# hardware.net
KiCad netlist of a schematic drawn in Altium Designer
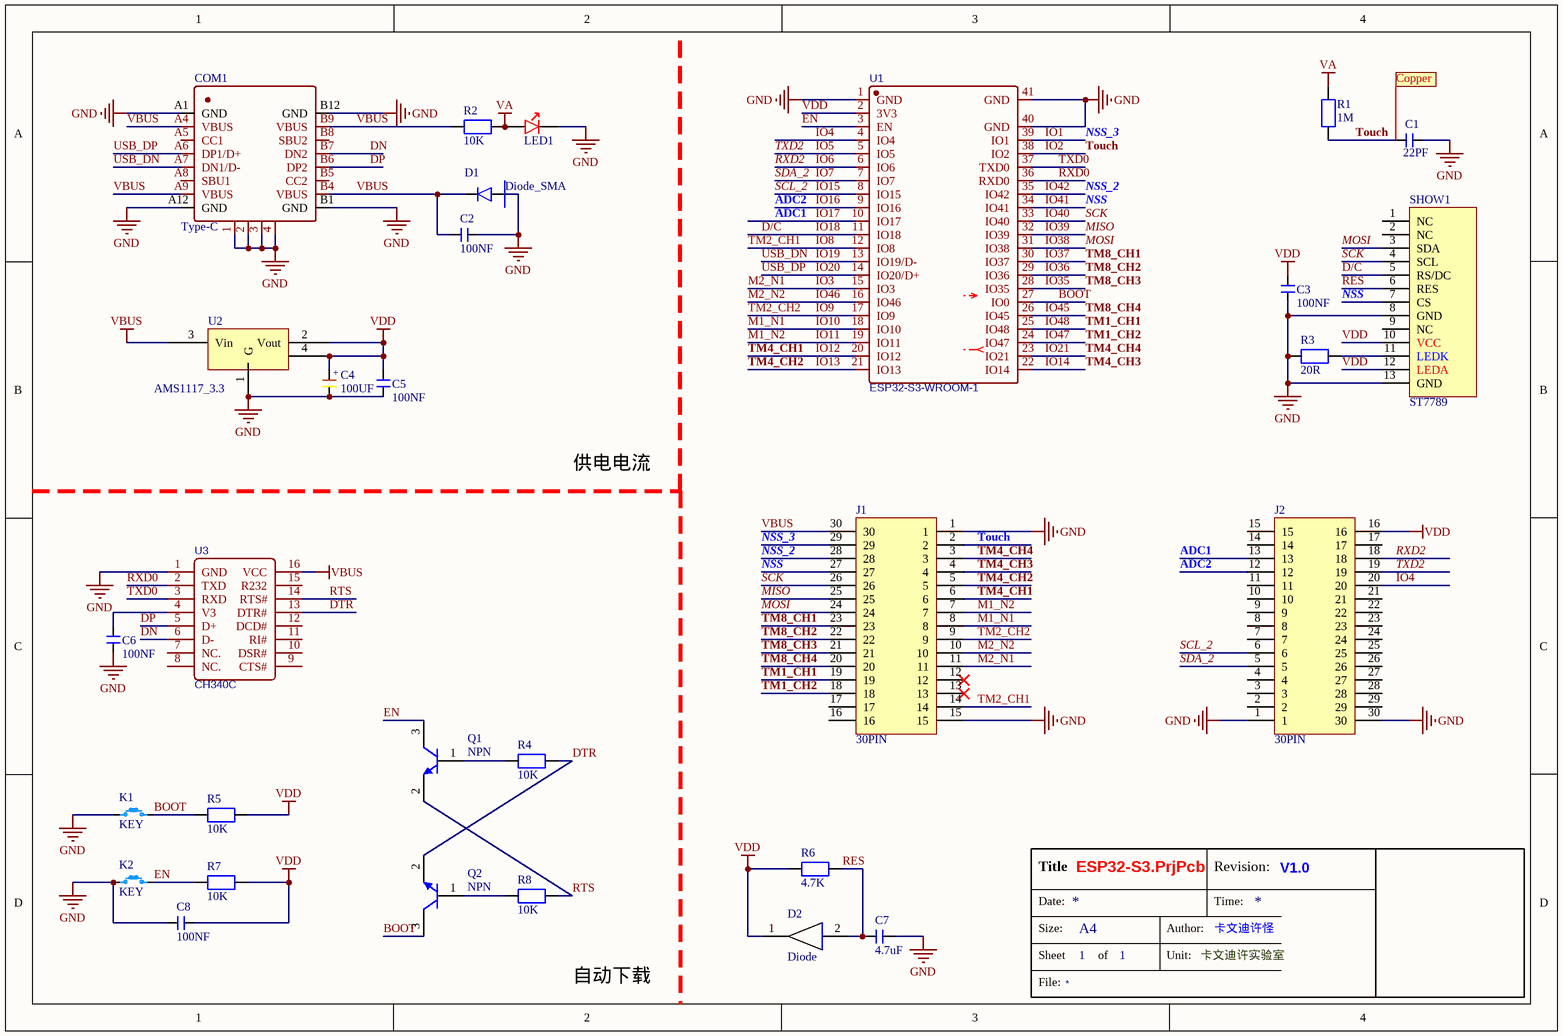
[diagram p0: hardware.SchDoc]

(export (version "E")
  (design (tool "Eeschema 10.0.6"))
  (components
    (comp (ref "C1")
      (value "22PF")
      (footprint "CAP_0603")
      (description "CAP  12~50V")
      (libsource (lib "User") (part "CAP"))
    )
    (comp (ref "C2")
      (value "100NF")
      (footprint "CAP_0603")
      (description "CAP  12~50V")
      (libsource (lib "User") (part "CAP"))
    )
    (comp (ref "C3")
      (value "100NF")
      (footprint "CAP_0603")
      (description "CAP  12~50V")
      (libsource (lib "User") (part "CAP"))
    )
    (comp (ref "C4")
      (value "100UF")
      (footprint "CAP_3528_B")
      (description "CAP  6~12V  钽电容")
      (libsource (lib "User") (part "CAP_TA"))
    )
    (comp (ref "C5")
      (value "100NF")
      (footprint "CAP_0603")
      (description "CAP  12~50V")
      (libsource (lib "User") (part "CAP"))
    )
    (comp (ref "C6")
      (value "100NF")
      (footprint "CAP_0603")
      (description "CAP  12~50V")
      (libsource (lib "User") (part "CAP"))
    )
    (comp (ref "C7")
      (value "4.7uF")
      (footprint "CAP_0603")
      (description "CAP")
      (libsource (lib "Schlib1") (part "CAP_SDM"))
    )
    (comp (ref "C8")
      (value "100NF")
      (footprint "CAP_0603")
      (description "CAP  12~50V")
      (libsource (lib "User") (part "CAP"))
    )
    (comp (ref "COM1")
      (value "Type-C")
      (footprint "USB-Type-C_16A")
      (description "USB")
      (libsource (lib "User") (part "USB-type_c"))
    )
    (comp (ref "D1")
      (value "Diode_SMA")
      (footprint "DIODE_SOD123")
      (description "Diode_肖特基")
      (libsource (lib "User") (part "Diode-SM"))
    )
    (comp (ref "D2")
      (value "Diode")
      (footprint "SOD123")
      (description "开关二极管")
      (libsource (lib "Schlib1") (part "Diode-SOD"))
    )
    (comp (ref "J1")
      (value "30PIN")
      (footprint "BTB_Double_30Pin_Up")
      (libsource (lib "") (part "BTB_DOUBLE_30PIN_1"))
    )
    (comp (ref "J2")
      (value "30PIN")
      (footprint "BTB_Double_30Pin_Up")
      (libsource (lib "User") (part "BTB_DOUBLE_30PIN"))
    )
    (comp (ref "K1")
      (value "KEY")
      (footprint "SW_PB_3X6")
      (description "Key")
      (libsource (lib "User") (part "KEY"))
    )
    (comp (ref "K2")
      (value "KEY")
      (footprint "SW_PB_3X6")
      (description "Key")
      (libsource (lib "User") (part "KEY"))
    )
    (comp (ref "LED1")
      (value "LED_R/G/B/Y")
      (footprint "LED_0603_R")
      (description "LED")
      (libsource (lib "User") (part "LED"))
    )
    (comp (ref "Q1") (value "NPN") (footprint "SOT23_3") (libsource (lib "User") (part "NPN")))
    (comp (ref "Q2") (value "NPN") (footprint "SOT23_3") (libsource (lib "User") (part "NPN")))
    (comp (ref "R1")
      (value "1M")
      (footprint "RESC_0603_2")
      (description "RES 贴片")
      (libsource (lib "User") (part "RES_S"))
    )
    (comp (ref "R2")
      (value "10K")
      (footprint "RESC_0603_2")
      (description "RES 贴片")
      (libsource (lib "User") (part "RES_S"))
    )
    (comp (ref "R3")
      (value "20R")
      (footprint "RESC_0603_2")
      (description "RES 贴片")
      (libsource (lib "User") (part "RES_S"))
    )
    (comp (ref "R4")
      (value "10K")
      (footprint "RESC_0603_2")
      (description "RES 贴片")
      (libsource (lib "User") (part "RES_S"))
    )
    (comp (ref "R5")
      (value "10K")
      (footprint "RESC_0603_2")
      (description "RES 贴片")
      (libsource (lib "User") (part "RES_S"))
    )
    (comp (ref "R6")
      (value "4.7K")
      (footprint "RESC_0603_2")
      (description "RES 贴片")
      (libsource (lib "User") (part "RES_S"))
    )
    (comp (ref "R7")
      (value "10K")
      (footprint "RESC_0603_2")
      (description "RES 贴片")
      (libsource (lib "User") (part "RES_S"))
    )
    (comp (ref "R8")
      (value "10K")
      (footprint "RESC_0603_2")
      (description "RES 贴片")
      (libsource (lib "User") (part "RES_S"))
    )
    (comp (ref "SHOW1")
      (value "ST7789")
      (footprint "LCD_1.14")
      (description "SHOW")
      (libsource (lib "User") (part "LCD_1.14"))
    )
    (comp (ref "U1")
      (value "ESP32-S3-WROOM-1")
      (footprint "ESP32-S3-WROOM-1")
      (fields
        (field (name "BOM_SUPPLIER PART") "C473005")
        (field (name "BOM_MANUFACTURER PART") "ESP32-SOLO-1")
        (field (name "CONTRIBUTOR") "LCSC")
      )
      (libsource (lib "User") (part "ESP32-S3-WROOM-1"))
    )
    (comp (ref "U2")
      (value "AMS1117_3.3")
      (footprint "SOT223_3")
      (description "DC-DC")
      (libsource (lib "User") (part "AMS1117_3.3"))
    )
    (comp (ref "U3")
      (value "CH340C")
      (footprint "SOIC_16")
      (fields (field (name "BOM_SUPPLIER PART") "C84681"))
      (libsource (lib "User") (part "CH340C"))
    )
  )
  (nets
    (net (code "1") (name "/ADC1") (class "Default")
      (node (ref "J2") (pin "13") (pinfunction "13_13") (pintype "passive"))
      (node (ref "U1") (pin "10") (pinfunction "IO17_10") (pintype "passive"))
    )
    (net (code "2") (name "/ADC2") (class "Default")
      (node (ref "J2") (pin "12") (pinfunction "12_12") (pintype "passive"))
      (node (ref "U1") (pin "9") (pinfunction "IO16_9") (pintype "passive"))
    )
    (net (code "3") (name "/BOOT") (class "Default")
      (node (ref "K1") (pin "1") (pintype "passive"))
      (node (ref "Q2") (pin "3") (pinfunction "C_3") (pintype "passive"))
      (node (ref "R5") (pin "1") (pinfunction "1_1") (pintype "passive"))
      (node (ref "U1") (pin "27") (pinfunction "IO0_27") (pintype "passive"))
    )
    (net (code "4") (name "/DN") (class "Default")
      (node (ref "COM1") (pin "B7") (pinfunction "DN2_B7") (pintype "passive"))
      (node (ref "U3") (pin "6") (pinfunction "D-_6") (pintype "passive"))
    )
    (net (code "5") (name "/DP") (class "Default")
      (node (ref "COM1") (pin "B6") (pinfunction "DP2_B6") (pintype "passive"))
      (node (ref "U3") (pin "5") (pinfunction "D+_5") (pintype "passive"))
    )
    (net (code "6") (name "/DTR") (class "Default")
      (node (ref "Q2") (pin "2") (pinfunction "E_2") (pintype "passive"))
      (node (ref "R4") (pin "2") (pinfunction "2_2") (pintype "passive"))
      (node (ref "U3") (pin "13") (pinfunction "DTR#_13") (pintype "passive"))
    )
    (net (code "7") (name "/D{slash}C") (class "Default")
      (node (ref "SHOW1") (pin "5") (pinfunction "RS/DC_5") (pintype "passive"))
      (node (ref "U1") (pin "11") (pinfunction "IO18_11") (pintype "passive"))
    )
    (net (code "8") (name "/EN") (class "Default")
      (node (ref "K2") (pin "1") (pintype "passive"))
      (node (ref "Q1") (pin "3") (pinfunction "C_3") (pintype "passive"))
      (node (ref "R7") (pin "1") (pinfunction "1_1") (pintype "passive"))
      (node (ref "U1") (pin "3") (pinfunction "EN_3") (pintype "passive"))
    )
    (net (code "9") (name "/IO1") (class "Default")
      (node (ref "J1") (pin "29") (pinfunction "29_29") (pintype "passive"))
      (node (ref "U1") (pin "39") (pinfunction "IO1_39") (pintype "passive"))
    )
    (net (code "10") (name "/IO2") (class "Default")
      (node (ref "C1") (pin "1") (pinfunction "0_1") (pintype "passive"))
      (node (ref "J1") (pin "2") (pinfunction "2_2") (pintype "passive"))
      (node (ref "R1") (pin "1") (pinfunction "1_1") (pintype "passive"))
      (node (ref "U1") (pin "38") (pinfunction "IO2_38") (pintype "passive"))
    )
    (net (code "11") (name "/IO3") (class "Default")
      (node (ref "J1") (pin "11") (pinfunction "11_11") (pintype "passive"))
      (node (ref "U1") (pin "15") (pinfunction "IO3_15") (pintype "passive"))
    )
    (net (code "12") (name "/IO4") (class "Default")
      (node (ref "J2") (pin "20") (pinfunction "20_20") (pintype "passive"))
      (node (ref "U1") (pin "4") (pinfunction "IO4_4") (pintype "passive"))
    )
    (net (code "13") (name "/IO5") (class "Default")
      (node (ref "J2") (pin "19") (pinfunction "19_19") (pintype "passive"))
      (node (ref "U1") (pin "5") (pinfunction "IO5_5") (pintype "passive"))
    )
    (net (code "14") (name "/IO6") (class "Default")
      (node (ref "J2") (pin "18") (pinfunction "18_18") (pintype "passive"))
      (node (ref "U1") (pin "6") (pinfunction "IO6_6") (pintype "passive"))
    )
    (net (code "15") (name "/IO7") (class "Default")
      (node (ref "J2") (pin "5") (pinfunction "5_5") (pintype "passive"))
      (node (ref "U1") (pin "7") (pinfunction "IO7_7") (pintype "passive"))
    )
    (net (code "16") (name "/IO8") (class "Default")
      (node (ref "J1") (pin "14") (pinfunction "14_14") (pintype "passive"))
      (node (ref "U1") (pin "12") (pinfunction "IO8_12") (pintype "passive"))
    )
    (net (code "17") (name "/IO9") (class "Default")
      (node (ref "J1") (pin "9") (pinfunction "9_9") (pintype "passive"))
      (node (ref "U1") (pin "17") (pinfunction "IO9_17") (pintype "passive"))
    )
    (net (code "18") (name "/IO10") (class "Default")
      (node (ref "J1") (pin "8") (pinfunction "8_8") (pintype "passive"))
      (node (ref "U1") (pin "18") (pinfunction "IO10_18") (pintype "passive"))
    )
    (net (code "19") (name "/IO11") (class "Default")
      (node (ref "J1") (pin "7") (pinfunction "7_7") (pintype "passive"))
      (node (ref "U1") (pin "19") (pinfunction "IO11_19") (pintype "passive"))
    )
    (net (code "20") (name "/IO12") (class "Default")
      (node (ref "J1") (pin "6") (pinfunction "6_6") (pintype "passive"))
      (node (ref "U1") (pin "20") (pinfunction "IO12_20") (pintype "passive"))
    )
    (net (code "21") (name "/IO13") (class "Default")
      (node (ref "J1") (pin "5") (pinfunction "5_5") (pintype "passive"))
      (node (ref "U1") (pin "21") (pinfunction "IO13_21") (pintype "passive"))
    )
    (net (code "22") (name "/IO14") (class "Default")
      (node (ref "J1") (pin "4") (pinfunction "4_4") (pintype "passive"))
      (node (ref "U1") (pin "22") (pinfunction "IO14_22") (pintype "passive"))
    )
    (net (code "23") (name "/IO15") (class "Default")
      (node (ref "J2") (pin "6") (pinfunction "6_6") (pintype "passive"))
      (node (ref "U1") (pin "8") (pinfunction "IO15_8") (pintype "passive"))
    )
    (net (code "24") (name "/IO19") (class "Default")
      (node (ref "COM1") (pin "A7") (pinfunction "DN1/D-_A7") (pintype "passive"))
      (node (ref "U1") (pin "13") (pinfunction "IO19/D-_13") (pintype "passive"))
    )
    (net (code "25") (name "/IO20") (class "Default")
      (node (ref "COM1") (pin "A6") (pinfunction "DP1/D+_A6") (pintype "passive"))
      (node (ref "U1") (pin "14") (pinfunction "IO20/D+_14") (pintype "passive"))
    )
    (net (code "26") (name "/IO21") (class "Default")
      (node (ref "J1") (pin "3") (pinfunction "3_3") (pintype "passive"))
      (node (ref "U1") (pin "23") (pinfunction "IO21_23") (pintype "passive"))
    )
    (net (code "27") (name "/IO35") (class "Default")
      (node (ref "J1") (pin "21") (pinfunction "21_21") (pintype "passive"))
      (node (ref "U1") (pin "28") (pinfunction "IO35_28") (pintype "passive"))
    )
    (net (code "28") (name "/IO36") (class "Default")
      (node (ref "J1") (pin "22") (pinfunction "22_22") (pintype "passive"))
      (node (ref "U1") (pin "29") (pinfunction "IO36_29") (pintype "passive"))
    )
    (net (code "29") (name "/IO37") (class "Default")
      (node (ref "J1") (pin "23") (pinfunction "23_23") (pintype "passive"))
      (node (ref "U1") (pin "30") (pinfunction "IO37_30") (pintype "passive"))
    )
    (net (code "30") (name "/IO38") (class "Default")
      (node (ref "J1") (pin "24") (pinfunction "24_24") (pintype "passive"))
      (node (ref "SHOW1") (pin "3") (pinfunction "SDA_3") (pintype "passive"))
      (node (ref "U1") (pin "31") (pinfunction "IO38_31") (pintype "passive"))
    )
    (net (code "31") (name "/IO39") (class "Default")
      (node (ref "J1") (pin "25") (pinfunction "25_25") (pintype "passive"))
      (node (ref "U1") (pin "32") (pinfunction "IO39_32") (pintype "passive"))
    )
    (net (code "32") (name "/IO40") (class "Default")
      (node (ref "J1") (pin "26") (pinfunction "26_26") (pintype "passive"))
      (node (ref "SHOW1") (pin "4") (pinfunction "SCL_4") (pintype "passive"))
      (node (ref "U1") (pin "33") (pinfunction "IO40_33") (pintype "passive"))
    )
    (net (code "33") (name "/IO41") (class "Default")
      (node (ref "J1") (pin "27") (pinfunction "27_27") (pintype "passive"))
      (node (ref "SHOW1") (pin "7") (pinfunction "CS_7") (pintype "passive"))
      (node (ref "U1") (pin "34") (pinfunction "IO41_34") (pintype "passive"))
    )
    (net (code "34") (name "/IO42") (class "Default")
      (node (ref "J1") (pin "28") (pinfunction "28_28") (pintype "passive"))
      (node (ref "U1") (pin "35") (pinfunction "IO42_35") (pintype "passive"))
    )
    (net (code "35") (name "/IO45") (class "Default")
      (node (ref "J1") (pin "20") (pinfunction "20_20") (pintype "passive"))
      (node (ref "U1") (pin "26") (pinfunction "IO45_26") (pintype "passive"))
    )
    (net (code "36") (name "/IO46") (class "Default")
      (node (ref "J1") (pin "10") (pinfunction "10_10") (pintype "passive"))
      (node (ref "U1") (pin "16") (pinfunction "IO46_16") (pintype "passive"))
    )
    (net (code "37") (name "/IO47") (class "Default")
      (node (ref "J1") (pin "18") (pinfunction "18_18") (pintype "passive"))
      (node (ref "U1") (pin "24") (pinfunction "IO47_24") (pintype "passive"))
    )
    (net (code "38") (name "/IO48") (class "Default")
      (node (ref "J1") (pin "19") (pinfunction "19_19") (pintype "passive"))
      (node (ref "U1") (pin "25") (pinfunction "IO48_25") (pintype "passive"))
    )
    (net (code "39") (name "/RES") (class "Default")
      (node (ref "C7") (pin "2") (pinfunction "0_2") (pintype "passive"))
      (node (ref "D2") (pin "2") (pinfunction "P_2") (pintype "passive"))
      (node (ref "R6") (pin "2") (pinfunction "2_2") (pintype "passive"))
      (node (ref "SHOW1") (pin "6") (pinfunction "RES_6") (pintype "passive"))
    )
    (net (code "40") (name "/RTS") (class "Default")
      (node (ref "Q1") (pin "2") (pinfunction "E_2") (pintype "passive"))
      (node (ref "R8") (pin "2") (pinfunction "2_2") (pintype "passive"))
      (node (ref "U3") (pin "14") (pinfunction "RTS#_14") (pintype "passive"))
    )
    (net (code "41") (name "/RXD0") (class "Default")
      (node (ref "U1") (pin "36") (pinfunction "RXD0_36") (pintype "passive"))
      (node (ref "U3") (pin "2") (pinfunction "TXD_2") (pintype "passive"))
    )
    (net (code "42") (name "/TXD0") (class "Default")
      (node (ref "U1") (pin "37") (pinfunction "TXD0_37") (pintype "passive"))
      (node (ref "U3") (pin "3") (pinfunction "RXD_3") (pintype "passive"))
    )
    (net (code "43") (name "GND") (class "Default")
      (node (ref "C1") (pin "2") (pinfunction "0_2") (pintype "passive"))
      (node (ref "C2") (pin "1") (pinfunction "0_1") (pintype "passive"))
      (node (ref "C3") (pin "2") (pinfunction "0_2") (pintype "passive"))
      (node (ref "C4") (pin "2") (pinfunction "0_2") (pintype "passive"))
      (node (ref "C5") (pin "2") (pinfunction "0_2") (pintype "passive"))
      (node (ref "C6") (pin "2") (pinfunction "0_2") (pintype "passive"))
      (node (ref "C7") (pin "1") (pinfunction "0_1") (pintype "passive"))
      (node (ref "C8") (pin "2") (pinfunction "0_2") (pintype "passive"))
      (node (ref "COM1") (pin "1") (pinfunction "1_1") (pintype "passive"))
      (node (ref "COM1") (pin "2") (pinfunction "2_2") (pintype "passive"))
      (node (ref "COM1") (pin "3") (pinfunction "3_3") (pintype "passive"))
      (node (ref "COM1") (pin "4") (pinfunction "4_4") (pintype "passive"))
      (node (ref "COM1") (pin "A1") (pinfunction "GND_A1") (pintype "passive"))
      (node (ref "COM1") (pin "A12") (pinfunction "GND_A12") (pintype "passive"))
      (node (ref "COM1") (pin "B1") (pinfunction "GND_B1") (pintype "passive"))
      (node (ref "COM1") (pin "B12") (pinfunction "GND_B12") (pintype "passive"))
      (node (ref "D1") (pin "1") (pinfunction "P_1") (pintype "passive"))
      (node (ref "J1") (pin "1") (pinfunction "1_1") (pintype "passive"))
      (node (ref "J1") (pin "15") (pinfunction "15_15") (pintype "passive"))
      (node (ref "J2") (pin "1") (pinfunction "1_1") (pintype "passive"))
      (node (ref "J2") (pin "30") (pinfunction "30_30") (pintype "passive"))
      (node (ref "K1") (pin "2") (pintype "passive"))
      (node (ref "K2") (pin "2") (pintype "passive"))
      (node (ref "LED1") (pin "1") (pinfunction "-_1") (pintype "passive"))
      (node (ref "R3") (pin "1") (pinfunction "1_1") (pintype "passive"))
      (node (ref "SHOW1") (pin "13") (pinfunction "GND_13") (pintype "passive"))
      (node (ref "SHOW1") (pin "8") (pinfunction "GND_8") (pintype "passive"))
      (node (ref "U1") (pin "1") (pinfunction "GND_1") (pintype "passive"))
      (node (ref "U1") (pin "40") (pinfunction "GND_40") (pintype "passive"))
      (node (ref "U1") (pin "41") (pinfunction "GND_41") (pintype "passive"))
      (node (ref "U2") (pin "1") (pinfunction "G_1") (pintype "passive"))
      (node (ref "U3") (pin "1") (pinfunction "GND_1") (pintype "passive"))
    )
    (net (code "44") (name "Net-(Q1-B)") (class "Default")
      (node (ref "Q1") (pin "1") (pinfunction "B_1") (pintype "passive"))
      (node (ref "R4") (pin "1") (pinfunction "1_1") (pintype "passive"))
    )
    (net (code "45") (name "Net-(Q2-B)") (class "Default")
      (node (ref "Q2") (pin "1") (pinfunction "B_1") (pintype "passive"))
      (node (ref "R8") (pin "1") (pinfunction "1_1") (pintype "passive"))
    )
    (net (code "46") (name "Net-(SHOW1-LEDK)") (class "Default")
      (node (ref "R3") (pin "2") (pinfunction "2_2") (pintype "passive"))
      (node (ref "SHOW1") (pin "11") (pinfunction "LEDK_11") (pintype "passive"))
    )
    (net (code "47") (name "Net-(U3-V3)") (class "Default")
      (node (ref "C6") (pin "1") (pinfunction "0_1") (pintype "passive"))
      (node (ref "U3") (pin "4") (pinfunction "V3_4") (pintype "passive"))
    )
    (net (code "48") (name "VA") (class "Default")
      (node (ref "LED1") (pin "2") (pinfunction "+_2") (pintype "passive"))
      (node (ref "R1") (pin "2") (pinfunction "2_2") (pintype "passive"))
      (node (ref "R2") (pin "2") (pinfunction "2_2") (pintype "passive"))
    )
    (net (code "49") (name "VBUS") (class "Default")
      (node (ref "C2") (pin "2") (pinfunction "0_2") (pintype "passive"))
      (node (ref "COM1") (pin "A4") (pinfunction "VBUS_A4") (pintype "passive"))
      (node (ref "COM1") (pin "A9") (pinfunction "VBUS_A9") (pintype "passive"))
      (node (ref "COM1") (pin "B4") (pinfunction "VBUS_B4") (pintype "passive"))
      (node (ref "COM1") (pin "B9") (pinfunction "VBUS_B9") (pintype "passive"))
      (node (ref "D1") (pin "2") (pinfunction "N_2") (pintype "passive"))
      (node (ref "J1") (pin "30") (pinfunction "30_30") (pintype "passive"))
      (node (ref "R2") (pin "1") (pinfunction "1_1") (pintype "passive"))
      (node (ref "U2") (pin "3") (pinfunction "Vin_3") (pintype "passive"))
      (node (ref "U3") (pin "16") (pinfunction "VCC_16") (pintype "passive"))
    )
    (net (code "50") (name "VDD") (class "Default")
      (node (ref "C3") (pin "1") (pinfunction "0_1") (pintype "passive"))
      (node (ref "C4") (pin "1") (pinfunction "0_1") (pintype "passive"))
      (node (ref "C5") (pin "1") (pinfunction "0_1") (pintype "passive"))
      (node (ref "C8") (pin "1") (pinfunction "0_1") (pintype "passive"))
      (node (ref "D2") (pin "1") (pinfunction "N_1") (pintype "passive"))
      (node (ref "J2") (pin "16") (pinfunction "16_16") (pintype "passive"))
      (node (ref "R5") (pin "2") (pinfunction "2_2") (pintype "passive"))
      (node (ref "R6") (pin "1") (pinfunction "1_1") (pintype "passive"))
      (node (ref "R7") (pin "2") (pinfunction "2_2") (pintype "passive"))
      (node (ref "SHOW1") (pin "10") (pinfunction "VCC_10") (pintype "passive"))
      (node (ref "SHOW1") (pin "12") (pinfunction "LEDA_12") (pintype "passive"))
      (node (ref "U1") (pin "2") (pinfunction "3V3_2") (pintype "passive"))
      (node (ref "U2") (pin "2") (pinfunction "Vout_2") (pintype "passive"))
      (node (ref "U2") (pin "4") (pinfunction "Vout_4") (pintype "passive"))
    )
    (net (code "51") (name "unconnected-(COM1-CC1-PadA5)") (class "Default")
      (node (ref "COM1") (pin "A5") (pinfunction "CC1_A5") (pintype "passive"))
    )
    (net (code "52") (name "unconnected-(COM1-CC2-PadB5)") (class "Default")
      (node (ref "COM1") (pin "B5") (pinfunction "CC2_B5") (pintype "passive"))
    )
    (net (code "53") (name "unconnected-(COM1-SBU1-PadA8)") (class "Default")
      (node (ref "COM1") (pin "A8") (pinfunction "SBU1_A8") (pintype "passive"))
    )
    (net (code "54") (name "unconnected-(COM1-SBU2-PadB8)") (class "Default")
      (node (ref "COM1") (pin "B8") (pinfunction "SBU2_B8") (pintype "passive"))
    )
    (net (code "55") (name "unconnected-(J1-Pad12)") (class "Default")
      (node (ref "J1") (pin "12") (pinfunction "12_12") (pintype "passive+no_connect"))
    )
    (net (code "56") (name "unconnected-(J1-Pad13)") (class "Default")
      (node (ref "J1") (pin "13") (pinfunction "13_13") (pintype "passive+no_connect"))
    )
    (net (code "57") (name "unconnected-(J1-Pad16)") (class "Default")
      (node (ref "J1") (pin "16") (pinfunction "16_16") (pintype "passive"))
    )
    (net (code "58") (name "unconnected-(J1-Pad17)") (class "Default")
      (node (ref "J1") (pin "17") (pinfunction "17_17") (pintype "passive"))
    )
    (net (code "59") (name "unconnected-(J2-Pad2)") (class "Default")
      (node (ref "J2") (pin "2") (pinfunction "2_2") (pintype "passive"))
    )
    (net (code "60") (name "unconnected-(J2-Pad3)") (class "Default")
      (node (ref "J2") (pin "3") (pinfunction "3_3") (pintype "passive"))
    )
    (net (code "61") (name "unconnected-(J2-Pad4)") (class "Default")
      (node (ref "J2") (pin "4") (pinfunction "4_4") (pintype "passive"))
    )
    (net (code "62") (name "unconnected-(J2-Pad7)") (class "Default")
      (node (ref "J2") (pin "7") (pinfunction "7_7") (pintype "passive"))
    )
    (net (code "63") (name "unconnected-(J2-Pad8)") (class "Default")
      (node (ref "J2") (pin "8") (pinfunction "8_8") (pintype "passive"))
    )
    (net (code "64") (name "unconnected-(J2-Pad9)") (class "Default")
      (node (ref "J2") (pin "9") (pinfunction "9_9") (pintype "passive"))
    )
    (net (code "65") (name "unconnected-(J2-Pad10)") (class "Default")
      (node (ref "J2") (pin "10") (pinfunction "10_10") (pintype "passive"))
    )
    (net (code "66") (name "unconnected-(J2-Pad11)") (class "Default")
      (node (ref "J2") (pin "11") (pinfunction "11_11") (pintype "passive"))
    )
    (net (code "67") (name "unconnected-(J2-Pad14)") (class "Default")
      (node (ref "J2") (pin "14") (pinfunction "14_14") (pintype "passive"))
    )
    (net (code "68") (name "unconnected-(J2-Pad15)") (class "Default")
      (node (ref "J2") (pin "15") (pinfunction "15_15") (pintype "passive"))
    )
    (net (code "69") (name "unconnected-(J2-Pad17)") (class "Default")
      (node (ref "J2") (pin "17") (pinfunction "17_17") (pintype "passive"))
    )
    (net (code "70") (name "unconnected-(J2-Pad21)") (class "Default")
      (node (ref "J2") (pin "21") (pinfunction "21_21") (pintype "passive"))
    )
    (net (code "71") (name "unconnected-(J2-Pad22)") (class "Default")
      (node (ref "J2") (pin "22") (pinfunction "22_22") (pintype "passive"))
    )
    (net (code "72") (name "unconnected-(J2-Pad23)") (class "Default")
      (node (ref "J2") (pin "23") (pinfunction "23_23") (pintype "passive"))
    )
    (net (code "73") (name "unconnected-(J2-Pad24)") (class "Default")
      (node (ref "J2") (pin "24") (pinfunction "24_24") (pintype "passive"))
    )
    (net (code "74") (name "unconnected-(J2-Pad25)") (class "Default")
      (node (ref "J2") (pin "25") (pinfunction "25_25") (pintype "passive"))
    )
    (net (code "75") (name "unconnected-(J2-Pad26)") (class "Default")
      (node (ref "J2") (pin "26") (pinfunction "26_26") (pintype "passive"))
    )
    (net (code "76") (name "unconnected-(J2-Pad27)") (class "Default")
      (node (ref "J2") (pin "27") (pinfunction "27_27") (pintype "passive"))
    )
    (net (code "77") (name "unconnected-(J2-Pad28)") (class "Default")
      (node (ref "J2") (pin "28") (pinfunction "28_28") (pintype "passive"))
    )
    (net (code "78") (name "unconnected-(J2-Pad29)") (class "Default")
      (node (ref "J2") (pin "29") (pinfunction "29_29") (pintype "passive"))
    )
    (net (code "79") (name "unconnected-(SHOW1-NC-Pad1)") (class "Default")
      (node (ref "SHOW1") (pin "1") (pinfunction "NC_1") (pintype "passive"))
    )
    (net (code "80") (name "unconnected-(SHOW1-NC-Pad2)") (class "Default")
      (node (ref "SHOW1") (pin "2") (pinfunction "NC_2") (pintype "passive"))
    )
    (net (code "81") (name "unconnected-(SHOW1-NC-Pad9)") (class "Default")
      (node (ref "SHOW1") (pin "9") (pinfunction "NC_9") (pintype "passive"))
    )
    (net (code "82") (name "unconnected-(U3-CTS#-Pad9)") (class "Default")
      (node (ref "U3") (pin "9") (pinfunction "CTS#_9") (pintype "passive"))
    )
    (net (code "83") (name "unconnected-(U3-DCD#-Pad12)") (class "Default")
      (node (ref "U3") (pin "12") (pinfunction "DCD#_12") (pintype "passive"))
    )
    (net (code "84") (name "unconnected-(U3-DSR#-Pad10)") (class "Default")
      (node (ref "U3") (pin "10") (pinfunction "DSR#_10") (pintype "passive"))
    )
    (net (code "85") (name "unconnected-(U3-NC.-Pad7)") (class "Default")
      (node (ref "U3") (pin "7") (pinfunction "NC._7") (pintype "passive"))
    )
    (net (code "86") (name "unconnected-(U3-NC.-Pad8)") (class "Default")
      (node (ref "U3") (pin "8") (pinfunction "NC._8") (pintype "passive"))
    )
    (net (code "87") (name "unconnected-(U3-R232-Pad15)") (class "Default")
      (node (ref "U3") (pin "15") (pinfunction "R232_15") (pintype "passive"))
    )
    (net (code "88") (name "unconnected-(U3-RI#-Pad11)") (class "Default")
      (node (ref "U3") (pin "11") (pinfunction "RI#_11") (pintype "passive"))
    )
  )
)
